# Single_Amplifier_Filter_2_0.net
KiCad netlist of a schematic drawn in Altium Designer
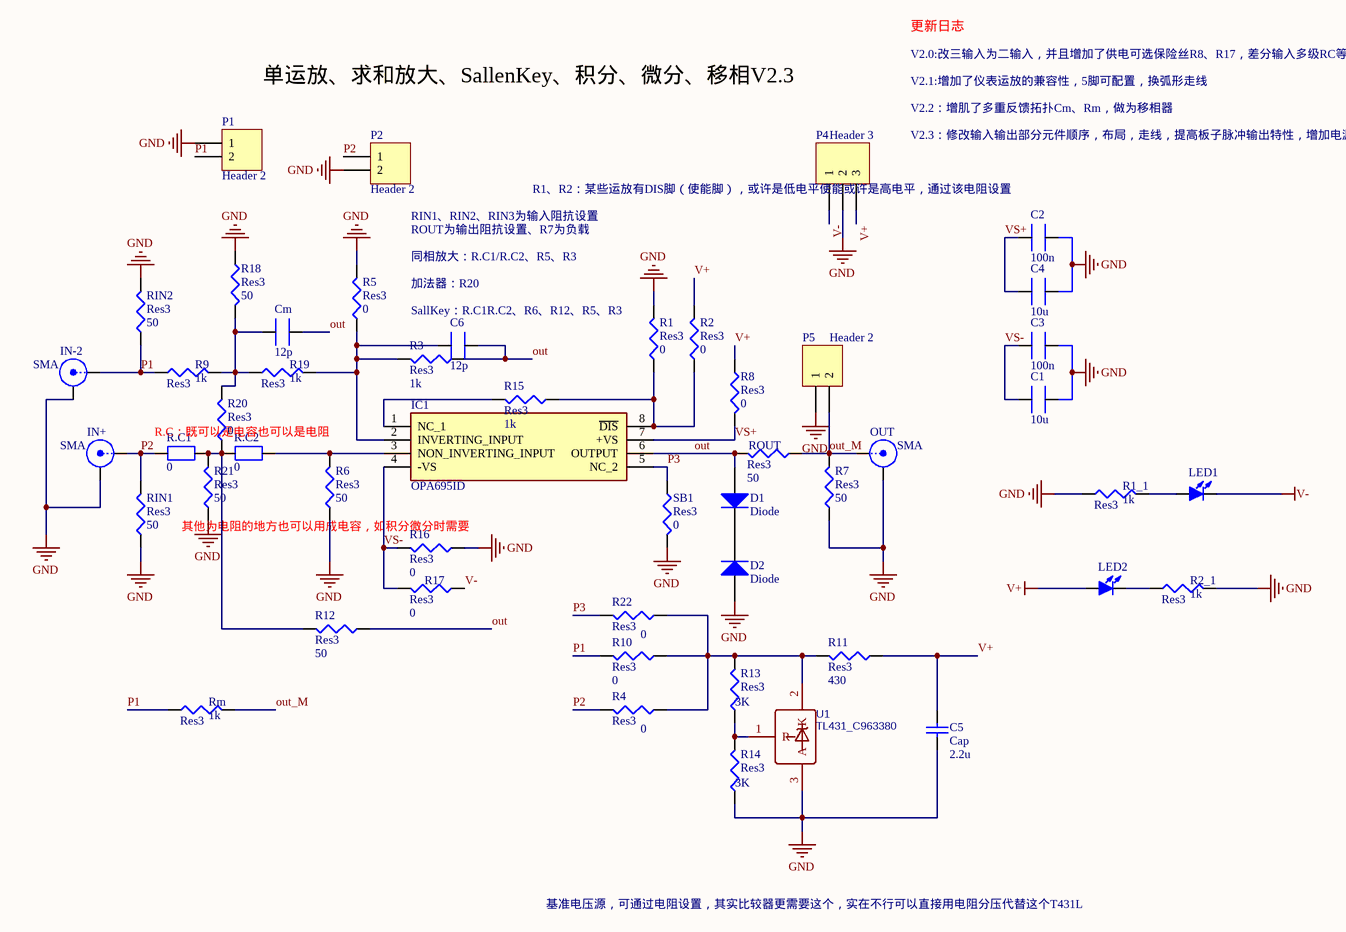
[diagram p0: Single_Amplifier(Filter)2.0.SchDoc]

(export (version "E")
  (design (tool "Eeschema 10.0.6"))
  (components
    (comp (ref "C1") (value "10u") (footprint "0805D") (libsource (lib "Lib1") (part "CAP_T")))
    (comp (ref "C2") (value "100n") (footprint "0805D") (libsource (lib "Lib1") (part "CAP_T")))
    (comp (ref "C3") (value "100n") (footprint "0805D") (libsource (lib "Lib1") (part "CAP_T")))
    (comp (ref "C4") (value "10u") (footprint "0805D") (libsource (lib "Lib1") (part "CAP_T")))
    (comp (ref "C5")
      (value "Cap")
      (footprint "0805D")
      (description "Capacitor")
      (fields (field (name "ALTIUM_VALUE") "2.2u") (field (name "PUBLISHER") "Altium Limited"))
      (libsource (lib "Miscellaneous Devices") (part "Cap"))
    )
    (comp (ref "C6") (value "12p") (footprint "0805D") (libsource (lib "Lib1") (part "CAP_T")))
    (comp (ref "Cm") (value "12p") (footprint "0805D") (libsource (lib "Lib1") (part "CAP_T")))
    (comp (ref "D1")
      (value "Diode")
      (footprint "1206A")
      (description "Default Diode")
      (fields (field (name "PUBLISHER") "Altium Limited"))
      (libsource (lib "Miscellaneous Devices") (part "Diode"))
    )
    (comp (ref "D2")
      (value "Diode")
      (footprint "1206A")
      (description "Default Diode")
      (fields (field (name "PUBLISHER") "Altium Limited"))
      (libsource (lib "Miscellaneous Devices") (part "Diode"))
    )
    (comp (ref "IC1")
      (value "OPA695ID")
      (footprint "SamacSys:SOIC127P600X175-8N")
      (description "Integrated Circuit")
      (fields (field (name "MOUSER PART NUMBER") "595-OPA695ID"))
      (libsource (lib "SamacSys") (part "OPA695ID"))
    )
    (comp (ref "IN+")
      (value "SMA")
      (footprint "SMA1")
      (description "BNC Elbow Connector")
      (fields (field (name "PUBLISHER") "Altium Limited"))
      (libsource (lib "Miscellaneous Connectors") (part "BNC"))
    )
    (comp (ref "IN-2")
      (value "SMA")
      (footprint "SMA1")
      (description "BNC Elbow Connector")
      (fields (field (name "PUBLISHER") "Altium Limited"))
      (libsource (lib "Miscellaneous Connectors") (part "BNC"))
    )
    (comp (ref "LED1")
      (value "~")
      (footprint "0805D")
      (description "贴片LED")
      (fields (field (name "版权归属") "源创客"))
      (libsource (lib "LED") (part "LED-SMD"))
    )
    (comp (ref "LED2")
      (value "~")
      (footprint "0805D")
      (description "贴片LED")
      (fields (field (name "版权归属") "源创客"))
      (libsource (lib "LED") (part "LED-SMD"))
    )
    (comp (ref "OUT")
      (value "SMA")
      (footprint "SMA1")
      (description "BNC Elbow Connector")
      (fields (field (name "PUBLISHER") "Altium Limited"))
      (libsource (lib "Miscellaneous Connectors") (part "BNC"))
    )
    (comp (ref "P1")
      (value "Header 2")
      (footprint "HDR1X2")
      (description "Header, 2-Pin")
      (fields (field (name "PUBLISHER") "Altium Limited"))
      (libsource (lib "Miscellaneous Connectors") (part "Header 2"))
    )
    (comp (ref "P2")
      (value "Header 2")
      (footprint "HDR1X2")
      (description "Header, 2-Pin")
      (fields (field (name "PUBLISHER") "Altium Limited"))
      (libsource (lib "Miscellaneous Connectors") (part "Header 2"))
    )
    (comp (ref "P4")
      (value "Header 3")
      (footprint "HDR1X3")
      (description "Header, 3-Pin")
      (fields (field (name "PUBLISHER") "Altium Limited"))
      (libsource (lib "Miscellaneous Connectors") (part "Header 3"))
    )
    (comp (ref "P5")
      (value "Header 2")
      (footprint "HDR1X2")
      (description "Header, 2-Pin")
      (fields (field (name "PUBLISHER") "Altium Limited"))
      (libsource (lib "") (part "Header 2_1"))
    )
    (comp (ref "R.C1") (value "0") (footprint "0805D") (libsource (lib "Lib1") (part "RES_T")))
    (comp (ref "R.C2") (value "0") (footprint "0805D") (libsource (lib "Lib1") (part "RES_T")))
    (comp (ref "R1")
      (value "Res3")
      (footprint "0805D")
      (description "Resistor")
      (fields (field (name "ALTIUM_VALUE") "0") (field (name "PUBLISHER") "Altium Limited"))
      (libsource (lib "Miscellaneous Devices") (part "Res3"))
    )
    (comp (ref "R1_1")
      (value "Res3")
      (footprint "0805D")
      (description "Resistor")
      (fields (field (name "ALTIUM_VALUE") "1k") (field (name "PUBLISHER") "Altium Limited"))
      (libsource (lib "Miscellaneous Devices") (part "Res3"))
    )
    (comp (ref "R2")
      (value "Res3")
      (footprint "0805D")
      (description "Resistor")
      (fields (field (name "ALTIUM_VALUE") "0") (field (name "PUBLISHER") "Altium Limited"))
      (libsource (lib "Miscellaneous Devices") (part "Res3"))
    )
    (comp (ref "R2_1")
      (value "Res3")
      (footprint "0805D")
      (description "Resistor")
      (fields (field (name "ALTIUM_VALUE") "1k") (field (name "PUBLISHER") "Altium Limited"))
      (libsource (lib "Miscellaneous Devices") (part "Res3"))
    )
    (comp (ref "R3")
      (value "Res3")
      (footprint "0805D")
      (description "Resistor")
      (fields (field (name "ALTIUM_VALUE") "1k") (field (name "PUBLISHER") "Altium Limited"))
      (libsource (lib "Miscellaneous Devices") (part "Res3"))
    )
    (comp (ref "R4")
      (value "Res3")
      (footprint "0805D")
      (description "Resistor")
      (fields (field (name "ALTIUM_VALUE") "0") (field (name "PUBLISHER") "Altium Limited"))
      (libsource (lib "Miscellaneous Devices") (part "Res3"))
    )
    (comp (ref "R5")
      (value "Res3")
      (footprint "0805D")
      (description "Resistor")
      (fields (field (name "ALTIUM_VALUE") "0") (field (name "PUBLISHER") "Altium Limited"))
      (libsource (lib "Miscellaneous Devices") (part "Res3"))
    )
    (comp (ref "R6")
      (value "Res3")
      (footprint "0805D")
      (description "Resistor")
      (fields (field (name "ALTIUM_VALUE") "50") (field (name "PUBLISHER") "Altium Limited"))
      (libsource (lib "Miscellaneous Devices") (part "Res3"))
    )
    (comp (ref "R7")
      (value "Res3")
      (footprint "0805D")
      (description "Resistor")
      (fields (field (name "ALTIUM_VALUE") "50") (field (name "PUBLISHER") "Altium Limited"))
      (libsource (lib "Miscellaneous Devices") (part "Res3"))
    )
    (comp (ref "R8")
      (value "Res3")
      (footprint "0805D")
      (description "Resistor")
      (fields (field (name "ALTIUM_VALUE") "0") (field (name "PUBLISHER") "Altium Limited"))
      (libsource (lib "Miscellaneous Devices") (part "Res3"))
    )
    (comp (ref "R9")
      (value "Res3")
      (footprint "0805D")
      (description "Resistor")
      (fields (field (name "ALTIUM_VALUE") "1k") (field (name "PUBLISHER") "Altium Limited"))
      (libsource (lib "Miscellaneous Devices") (part "Res3"))
    )
    (comp (ref "R10")
      (value "Res3")
      (footprint "0805D")
      (description "Resistor")
      (fields (field (name "ALTIUM_VALUE") "0") (field (name "PUBLISHER") "Altium Limited"))
      (libsource (lib "Miscellaneous Devices") (part "Res3"))
    )
    (comp (ref "R11")
      (value "Res3")
      (footprint "0805D")
      (description "Resistor")
      (fields (field (name "ALTIUM_VALUE") "430") (field (name "PUBLISHER") "Altium Limited"))
      (libsource (lib "Miscellaneous Devices") (part "Res3"))
    )
    (comp (ref "R12")
      (value "Res3")
      (footprint "0805D")
      (description "Resistor")
      (fields (field (name "ALTIUM_VALUE") "50") (field (name "PUBLISHER") "Altium Limited"))
      (libsource (lib "Miscellaneous Devices") (part "Res3"))
    )
    (comp (ref "R13")
      (value "Res3")
      (footprint "0805D")
      (description "Resistor")
      (fields (field (name "ALTIUM_VALUE") "3K") (field (name "PUBLISHER") "Altium Limited"))
      (libsource (lib "Miscellaneous Devices") (part "Res3"))
    )
    (comp (ref "R14")
      (value "Res3")
      (footprint "0805D")
      (description "Resistor")
      (fields (field (name "ALTIUM_VALUE") "3K") (field (name "PUBLISHER") "Altium Limited"))
      (libsource (lib "Miscellaneous Devices") (part "Res3"))
    )
    (comp (ref "R15")
      (value "Res3")
      (footprint "0805D")
      (description "Resistor")
      (fields (field (name "ALTIUM_VALUE") "1k") (field (name "PUBLISHER") "Altium Limited"))
      (libsource (lib "Miscellaneous Devices") (part "Res3"))
    )
    (comp (ref "R16")
      (value "Res3")
      (footprint "0805D")
      (description "Resistor")
      (fields (field (name "ALTIUM_VALUE") "0") (field (name "PUBLISHER") "Altium Limited"))
      (libsource (lib "Miscellaneous Devices") (part "Res3"))
    )
    (comp (ref "R17")
      (value "Res3")
      (footprint "0805D")
      (description "Resistor")
      (fields (field (name "ALTIUM_VALUE") "0") (field (name "PUBLISHER") "Altium Limited"))
      (libsource (lib "Miscellaneous Devices") (part "Res3"))
    )
    (comp (ref "R18")
      (value "Res3")
      (footprint "0805D")
      (description "Resistor")
      (fields (field (name "ALTIUM_VALUE") "50") (field (name "PUBLISHER") "Altium Limited"))
      (libsource (lib "Miscellaneous Devices") (part "Res3"))
    )
    (comp (ref "R19")
      (value "Res3")
      (footprint "0805D")
      (description "Resistor")
      (fields (field (name "ALTIUM_VALUE") "1k") (field (name "PUBLISHER") "Altium Limited"))
      (libsource (lib "Miscellaneous Devices") (part "Res3"))
    )
    (comp (ref "R20")
      (value "Res3")
      (footprint "0805D")
      (description "Resistor")
      (fields (field (name "ALTIUM_VALUE") "0") (field (name "PUBLISHER") "Altium Limited"))
      (libsource (lib "Miscellaneous Devices") (part "Res3"))
    )
    (comp (ref "R21")
      (value "Res3")
      (footprint "0805D")
      (description "Resistor")
      (fields (field (name "ALTIUM_VALUE") "50") (field (name "PUBLISHER") "Altium Limited"))
      (libsource (lib "Miscellaneous Devices") (part "Res3"))
    )
    (comp (ref "R22")
      (value "Res3")
      (footprint "0805D")
      (description "Resistor")
      (fields (field (name "ALTIUM_VALUE") "0") (field (name "PUBLISHER") "Altium Limited"))
      (libsource (lib "Miscellaneous Devices") (part "Res3"))
    )
    (comp (ref "RIN1")
      (value "Res3")
      (footprint "0805D")
      (description "Resistor")
      (fields (field (name "ALTIUM_VALUE") "50") (field (name "PUBLISHER") "Altium Limited"))
      (libsource (lib "Miscellaneous Devices") (part "Res3"))
    )
    (comp (ref "RIN2")
      (value "Res3")
      (footprint "0805D")
      (description "Resistor")
      (fields (field (name "ALTIUM_VALUE") "50") (field (name "PUBLISHER") "Altium Limited"))
      (libsource (lib "Miscellaneous Devices") (part "Res3"))
    )
    (comp (ref "Rm")
      (value "Res3")
      (footprint "0805D")
      (description "Resistor")
      (fields (field (name "ALTIUM_VALUE") "1k") (field (name "PUBLISHER") "Altium Limited"))
      (libsource (lib "Miscellaneous Devices") (part "Res3"))
    )
    (comp (ref "ROUT")
      (value "Res3")
      (footprint "0805D")
      (description "Resistor")
      (fields (field (name "ALTIUM_VALUE") "50") (field (name "PUBLISHER") "Altium Limited"))
      (libsource (lib "Miscellaneous Devices") (part "Res3"))
    )
    (comp (ref "SB1")
      (value "Res3")
      (footprint "0805D")
      (description "Resistor")
      (fields (field (name "ALTIUM_VALUE") "0") (field (name "PUBLISHER") "Altium Limited"))
      (libsource (lib "Miscellaneous Devices") (part "Res3"))
    )
    (comp (ref "U1")
      (value "TL431_C963380")
      (footprint "SOT-23")
      (fields
        (field (name "BOM_SUPPLIER PART") "C963380")
        (field (name "BOM_MANUFACTURER PART") "TL431")
        (field (name "CONTRIBUTOR") "LCSC")
      )
      (libsource (lib "TL431") (part "TL431"))
    )
  )
  (nets
    (net (code "1") (name "/P1") (class "Default")
      (node (ref "IN-2") (pin "1") (pinfunction "X_1") (pintype "passive"))
      (node (ref "P1") (pin "2") (pinfunction "2_2") (pintype "passive"))
      (node (ref "R10") (pin "2") (pinfunction "2_2") (pintype "passive"))
      (node (ref "R9") (pin "1") (pinfunction "1_1") (pintype "passive"))
      (node (ref "RIN2") (pin "1") (pinfunction "1_1") (pintype "passive"))
      (node (ref "Rm") (pin "1") (pinfunction "1_1") (pintype "passive"))
    )
    (net (code "2") (name "/P2") (class "Default")
      (node (ref "IN+") (pin "1") (pinfunction "X_1") (pintype "passive"))
      (node (ref "P2") (pin "1") (pinfunction "1_1") (pintype "passive"))
      (node (ref "R.C1") (pin "1") (pinfunction "SD_1") (pintype "passive"))
      (node (ref "R4") (pin "2") (pinfunction "2_2") (pintype "passive"))
      (node (ref "RIN1") (pin "2") (pinfunction "2_2") (pintype "passive"))
    )
    (net (code "3") (name "/P3") (class "Default")
      (node (ref "IC1") (pin "5") (pinfunction "NC_2_5") (pintype "passive"))
      (node (ref "R22") (pin "2") (pinfunction "2_2") (pintype "passive"))
      (node (ref "SB1") (pin "1") (pinfunction "1_1") (pintype "passive"))
    )
    (net (code "4") (name "/VS+") (class "Default")
      (node (ref "C2") (pin "1") (pinfunction "SD_1") (pintype "passive"))
      (node (ref "C4") (pin "1") (pinfunction "SD_1") (pintype "passive"))
      (node (ref "IC1") (pin "7") (pinfunction "+VS_7") (pintype "passive"))
      (node (ref "R8") (pin "2") (pinfunction "2_2") (pintype "passive"))
    )
    (net (code "5") (name "/VS-") (class "Default")
      (node (ref "C1") (pin "1") (pinfunction "SD_1") (pintype "passive"))
      (node (ref "C3") (pin "1") (pinfunction "SD_1") (pintype "passive"))
      (node (ref "IC1") (pin "4") (pinfunction "-VS_4") (pintype "passive"))
      (node (ref "R16") (pin "2") (pinfunction "2_2") (pintype "passive"))
      (node (ref "R17") (pin "2") (pinfunction "2_2") (pintype "passive"))
    )
    (net (code "6") (name "/out") (class "Default")
      (node (ref "C6") (pin "2") (pinfunction "SD_2") (pintype "passive"))
      (node (ref "Cm") (pin "2") (pinfunction "SD_2") (pintype "passive"))
      (node (ref "D1") (pin "1") (pinfunction "A_1") (pintype "passive"))
      (node (ref "IC1") (pin "6") (pinfunction "OUTPUT_6") (pintype "passive"))
      (node (ref "R12") (pin "1") (pinfunction "1_1") (pintype "passive"))
      (node (ref "R3") (pin "1") (pinfunction "1_1") (pintype "passive"))
      (node (ref "ROUT") (pin "2") (pinfunction "2_2") (pintype "passive"))
    )
    (net (code "7") (name "/out_M") (class "Default")
      (node (ref "OUT") (pin "1") (pinfunction "X_1") (pintype "passive"))
      (node (ref "P5") (pin "2") (pinfunction "2_2") (pintype "passive"))
      (node (ref "R7") (pin "2") (pinfunction "2_2") (pintype "passive"))
      (node (ref "ROUT") (pin "1") (pinfunction "1_1") (pintype "passive"))
      (node (ref "Rm") (pin "2") (pinfunction "2_2") (pintype "passive"))
    )
    (net (code "8") (name "GND") (class "Default")
      (node (ref "C1") (pin "2") (pinfunction "SD_2") (pintype "passive"))
      (node (ref "C2") (pin "2") (pinfunction "SD_2") (pintype "passive"))
      (node (ref "C3") (pin "2") (pinfunction "SD_2") (pintype "passive"))
      (node (ref "C4") (pin "2") (pinfunction "SD_2") (pintype "passive"))
      (node (ref "C5") (pin "1") (pinfunction "1_1") (pintype "passive"))
      (node (ref "D2") (pin "1") (pinfunction "A_1") (pintype "passive"))
      (node (ref "IN+") (pin "2") (pinfunction "Y_2") (pintype "passive"))
      (node (ref "IN-2") (pin "2") (pinfunction "Y_2") (pintype "passive"))
      (node (ref "OUT") (pin "2") (pinfunction "Y_2") (pintype "passive"))
      (node (ref "P1") (pin "1") (pinfunction "1_1") (pintype "passive"))
      (node (ref "P2") (pin "2") (pinfunction "2_2") (pintype "passive"))
      (node (ref "P4") (pin "2") (pinfunction "2_2") (pintype "passive"))
      (node (ref "P5") (pin "1") (pinfunction "1_1") (pintype "passive"))
      (node (ref "R1") (pin "2") (pinfunction "2_2") (pintype "passive"))
      (node (ref "R14") (pin "1") (pinfunction "1_1") (pintype "passive"))
      (node (ref "R16") (pin "1") (pinfunction "1_1") (pintype "passive"))
      (node (ref "R18") (pin "1") (pinfunction "1_1") (pintype "passive"))
      (node (ref "R1_1") (pin "1") (pinfunction "1_1") (pintype "passive"))
      (node (ref "R21") (pin "1") (pinfunction "1_1") (pintype "passive"))
      (node (ref "R2_1") (pin "2") (pinfunction "2_2") (pintype "passive"))
      (node (ref "R5") (pin "2") (pinfunction "2_2") (pintype "passive"))
      (node (ref "R6") (pin "1") (pinfunction "1_1") (pintype "passive"))
      (node (ref "R7") (pin "1") (pinfunction "1_1") (pintype "passive"))
      (node (ref "RIN1") (pin "1") (pinfunction "1_1") (pintype "passive"))
      (node (ref "RIN2") (pin "2") (pinfunction "2_2") (pintype "passive"))
      (node (ref "SB1") (pin "2") (pinfunction "2_2") (pintype "passive"))
      (node (ref "U1") (pin "3") (pinfunction "A_3") (pintype "passive"))
    )
    (net (code "9") (name "Net-(Cm-SD-Pad1)") (class "Default")
      (node (ref "Cm") (pin "1") (pinfunction "SD_1") (pintype "passive"))
      (node (ref "R18") (pin "2") (pinfunction "2_2") (pintype "passive"))
      (node (ref "R19") (pin "1") (pinfunction "1_1") (pintype "passive"))
      (node (ref "R20") (pin "2") (pinfunction "2_2") (pintype "passive"))
      (node (ref "R9") (pin "2") (pinfunction "2_2") (pintype "passive"))
    )
    (net (code "10") (name "Net-(D1-K)") (class "Default")
      (node (ref "D1") (pin "2") (pinfunction "K_2") (pintype "passive"))
      (node (ref "D2") (pin "2") (pinfunction "K_2") (pintype "passive"))
    )
    (net (code "11") (name "Net-(IC1-INVERTING_INPUT)") (class "Default")
      (node (ref "C6") (pin "1") (pinfunction "SD_1") (pintype "passive"))
      (node (ref "IC1") (pin "2") (pinfunction "INVERTING_INPUT_2") (pintype "passive"))
      (node (ref "R19") (pin "2") (pinfunction "2_2") (pintype "passive"))
      (node (ref "R3") (pin "2") (pinfunction "2_2") (pintype "passive"))
      (node (ref "R5") (pin "1") (pinfunction "1_1") (pintype "passive"))
    )
    (net (code "12") (name "Net-(IC1-NC_1)") (class "Default")
      (node (ref "IC1") (pin "1") (pinfunction "NC_1_1") (pintype "passive"))
      (node (ref "R15") (pin "2") (pinfunction "2_2") (pintype "passive"))
    )
    (net (code "13") (name "Net-(IC1-NON_INVERTING_INPUT)") (class "Default")
      (node (ref "IC1") (pin "3") (pinfunction "NON_INVERTING_INPUT_3") (pintype "passive"))
      (node (ref "R.C2") (pin "2") (pinfunction "SD_2") (pintype "passive"))
      (node (ref "R6") (pin "2") (pinfunction "2_2") (pintype "passive"))
    )
    (net (code "14") (name "Net-(IC1-~{DIS})") (class "Default")
      (node (ref "IC1") (pin "8") (pinfunction "~{DIS}_8") (pintype "passive"))
      (node (ref "R1") (pin "1") (pinfunction "1_1") (pintype "passive"))
      (node (ref "R15") (pin "1") (pinfunction "1_1") (pintype "passive"))
      (node (ref "R2") (pin "1") (pinfunction "1_1") (pintype "passive"))
    )
    (net (code "15") (name "Net-(LED1-A)") (class "Default")
      (node (ref "LED1") (pin "1") (pinfunction "A_1") (pintype "passive"))
      (node (ref "R1_1") (pin "2") (pinfunction "2_2") (pintype "passive"))
    )
    (net (code "16") (name "Net-(LED2-K)") (class "Default")
      (node (ref "LED2") (pin "2") (pinfunction "K_2") (pintype "passive"))
      (node (ref "R2_1") (pin "1") (pinfunction "1_1") (pintype "passive"))
    )
    (net (code "17") (name "Net-(R.C1-SD-Pad2)") (class "Default")
      (node (ref "R.C1") (pin "2") (pinfunction "SD_2") (pintype "passive"))
      (node (ref "R.C2") (pin "1") (pinfunction "SD_1") (pintype "passive"))
      (node (ref "R12") (pin "2") (pinfunction "2_2") (pintype "passive"))
      (node (ref "R20") (pin "1") (pinfunction "1_1") (pintype "passive"))
      (node (ref "R21") (pin "2") (pinfunction "2_2") (pintype "passive"))
    )
    (net (code "18") (name "Net-(U1-K)") (class "Default")
      (node (ref "R10") (pin "1") (pinfunction "1_1") (pintype "passive"))
      (node (ref "R11") (pin "2") (pinfunction "2_2") (pintype "passive"))
      (node (ref "R13") (pin "2") (pinfunction "2_2") (pintype "passive"))
      (node (ref "R22") (pin "1") (pinfunction "1_1") (pintype "passive"))
      (node (ref "R4") (pin "1") (pinfunction "1_1") (pintype "passive"))
      (node (ref "U1") (pin "2") (pinfunction "K_2") (pintype "passive"))
    )
    (net (code "19") (name "Net-(U1-R)") (class "Default")
      (node (ref "R13") (pin "1") (pinfunction "1_1") (pintype "passive"))
      (node (ref "R14") (pin "2") (pinfunction "2_2") (pintype "passive"))
      (node (ref "U1") (pin "1") (pinfunction "R_1") (pintype "passive"))
    )
    (net (code "20") (name "V+") (class "Default")
      (node (ref "C5") (pin "2") (pinfunction "2_2") (pintype "passive"))
      (node (ref "LED2") (pin "1") (pinfunction "A_1") (pintype "passive"))
      (node (ref "P4") (pin "3") (pinfunction "3_3") (pintype "passive"))
      (node (ref "R11") (pin "1") (pinfunction "1_1") (pintype "passive"))
      (node (ref "R2") (pin "2") (pinfunction "2_2") (pintype "passive"))
      (node (ref "R8") (pin "1") (pinfunction "1_1") (pintype "passive"))
    )
    (net (code "21") (name "V-") (class "Default")
      (node (ref "LED1") (pin "2") (pinfunction "K_2") (pintype "passive"))
      (node (ref "P4") (pin "1") (pinfunction "1_1") (pintype "passive"))
      (node (ref "R17") (pin "1") (pinfunction "1_1") (pintype "passive"))
    )
  )
)
